# Stim_EMG_breakout.net
KiCad netlist of a schematic drawn in EAGLE
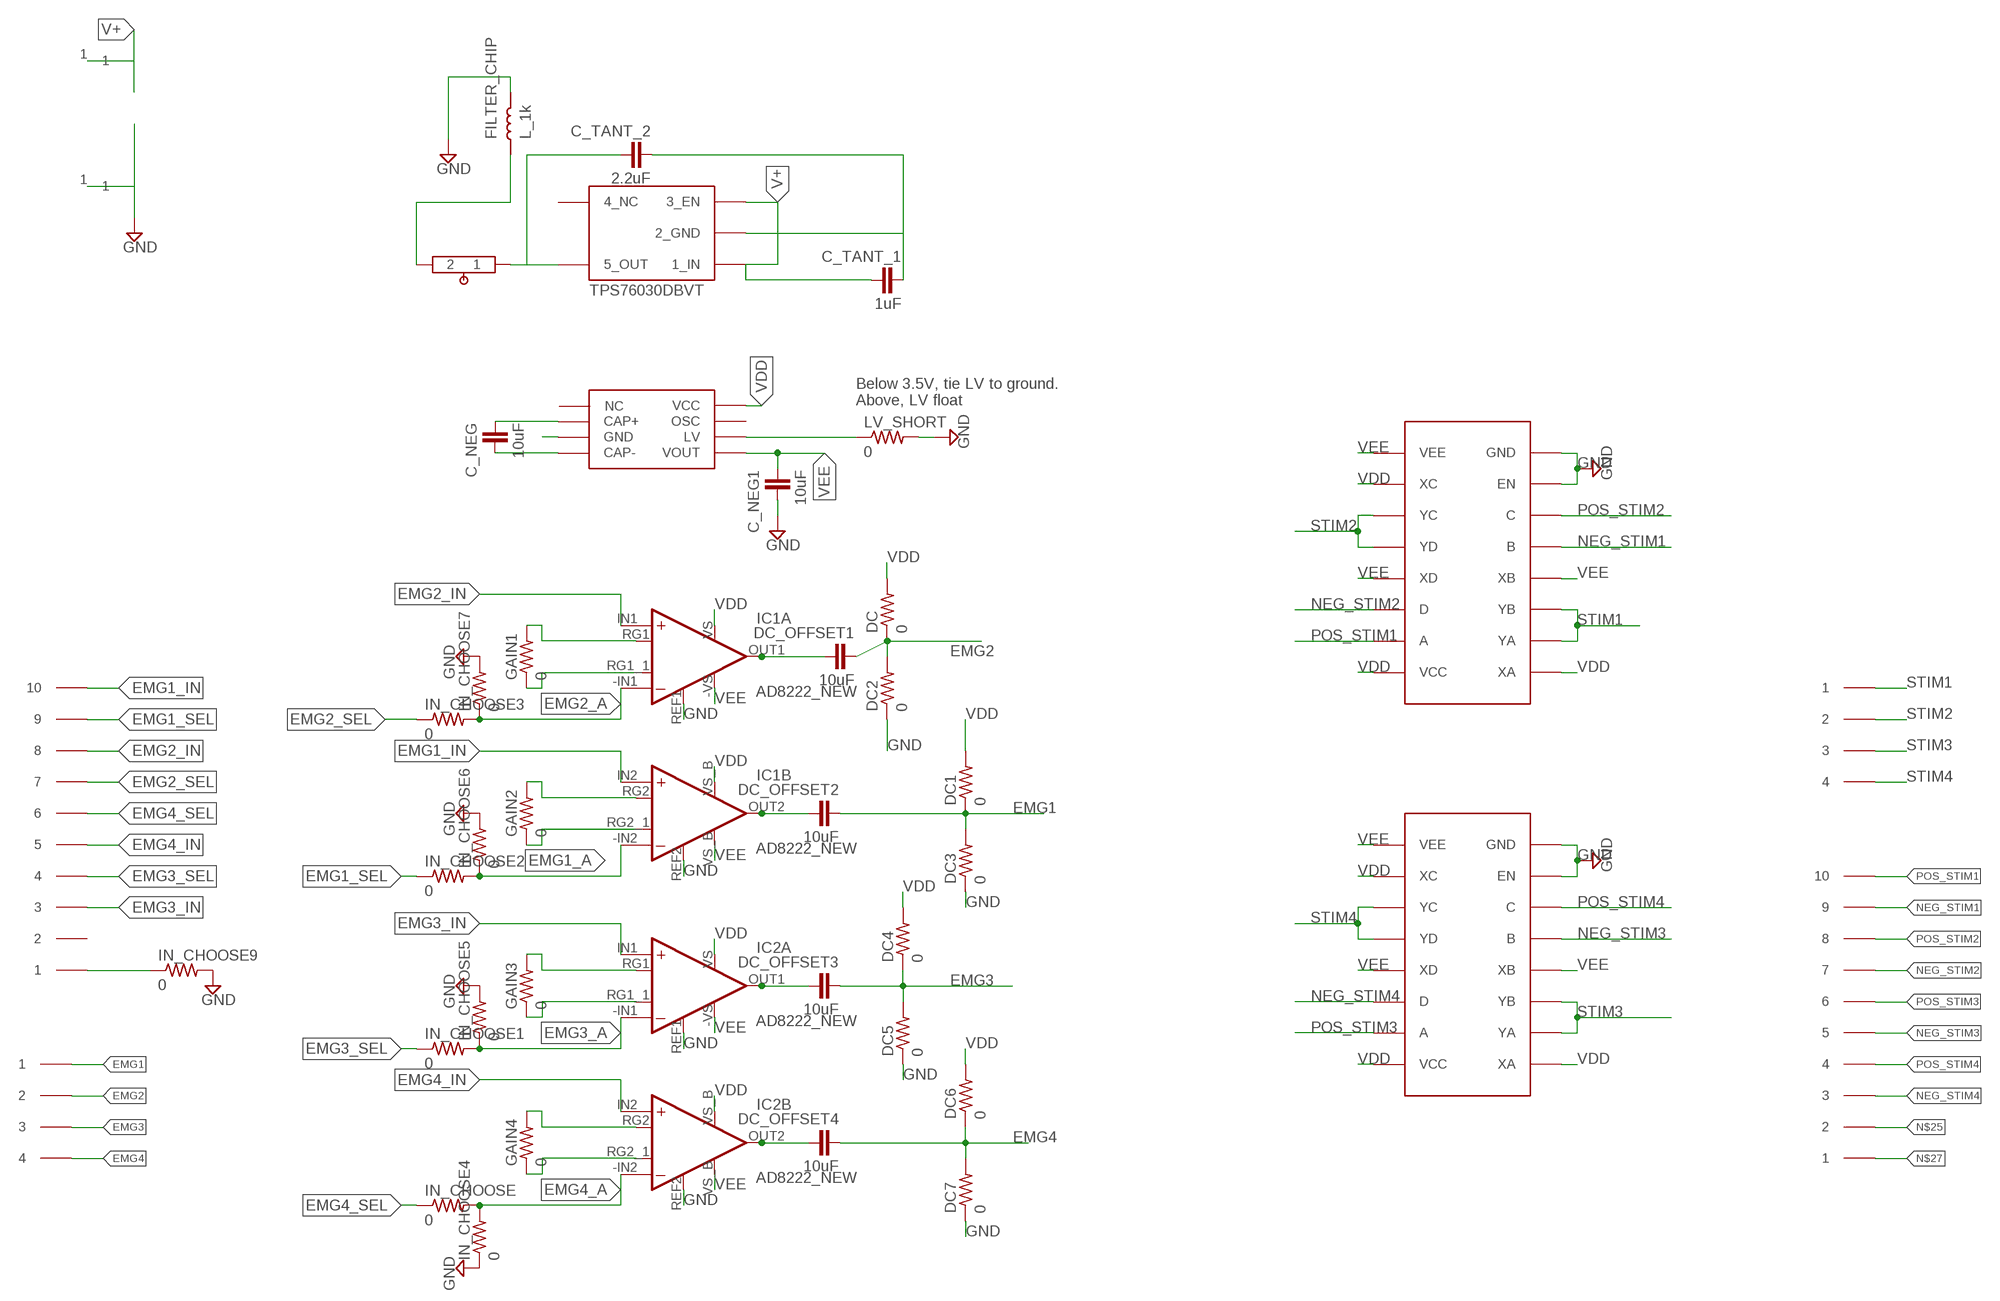
[diagram p0: schematic, sheet 1]

(export (version "E")
  (design (tool "Eeschema 10.0.6"))
  (components
    (comp (ref "C_NEG")
      (value "10uF")
      (footprint "eagle-import:0402_R_L_C")
      (libsource (lib "eagle-import") (part "0Y0X_C0402"))
    )
    (comp (ref "C_NEG1")
      (value "10uF")
      (footprint "eagle-import:0402_R_L_C")
      (libsource (lib "eagle-import") (part "0Y0X_C0402"))
    )
    (comp (ref "C_TANT_1")
      (value "1uF")
      (footprint "eagle-import:0603_R_L_C")
      (libsource (lib "eagle-import") (part "0Y0X_C0603"))
    )
    (comp (ref "C_TANT_2")
      (value "2.2uF")
      (footprint "eagle-import:0603_R_L_C")
      (libsource (lib "eagle-import") (part "0Y0X_C0603"))
    )
    (comp (ref "DC")
      (value "0")
      (footprint "eagle-import:0402_R_L_C")
      (libsource (lib "eagle-import") (part "0Y0X_R0402"))
    )
    (comp (ref "DC1")
      (value "0")
      (footprint "eagle-import:0402_R_L_C")
      (libsource (lib "eagle-import") (part "0Y0X_R0402"))
    )
    (comp (ref "DC2")
      (value "0")
      (footprint "eagle-import:0402_R_L_C")
      (libsource (lib "eagle-import") (part "0Y0X_R0402"))
    )
    (comp (ref "DC3")
      (value "0")
      (footprint "eagle-import:0402_R_L_C")
      (libsource (lib "eagle-import") (part "0Y0X_R0402"))
    )
    (comp (ref "DC4")
      (value "0")
      (footprint "eagle-import:0402_R_L_C")
      (libsource (lib "eagle-import") (part "0Y0X_R0402"))
    )
    (comp (ref "DC5")
      (value "0")
      (footprint "eagle-import:0402_R_L_C")
      (libsource (lib "eagle-import") (part "0Y0X_R0402"))
    )
    (comp (ref "DC6")
      (value "0")
      (footprint "eagle-import:0402_R_L_C")
      (libsource (lib "eagle-import") (part "0Y0X_R0402"))
    )
    (comp (ref "DC7")
      (value "0")
      (footprint "eagle-import:0402_R_L_C")
      (libsource (lib "eagle-import") (part "0Y0X_R0402"))
    )
    (comp (ref "DC_OFFSET1")
      (value "10uF")
      (footprint "eagle-import:0402_R_L_C")
      (libsource (lib "eagle-import") (part "0Y0X_C0402"))
    )
    (comp (ref "DC_OFFSET2")
      (value "10uF")
      (footprint "eagle-import:0402_R_L_C")
      (libsource (lib "eagle-import") (part "0Y0X_C0402"))
    )
    (comp (ref "DC_OFFSET3")
      (value "10uF")
      (footprint "eagle-import:0402_R_L_C")
      (libsource (lib "eagle-import") (part "0Y0X_C0402"))
    )
    (comp (ref "DC_OFFSET4")
      (value "10uF")
      (footprint "eagle-import:0402_R_L_C")
      (libsource (lib "eagle-import") (part "0Y0X_C0402"))
    )
    (comp (ref "FILTER_CHIP")
      (value "L_1k")
      (footprint "eagle-import:0402_R_L_C")
      (libsource (lib "eagle-import") (part "0Y0X_L0402"))
    )
    (comp (ref "GAIN1")
      (value "0")
      (footprint "eagle-import:0402_R_L_C")
      (libsource (lib "eagle-import") (part "0Y0X_R0402"))
    )
    (comp (ref "GAIN2")
      (value "0")
      (footprint "eagle-import:0402_R_L_C")
      (libsource (lib "eagle-import") (part "0Y0X_R0402"))
    )
    (comp (ref "GAIN3")
      (value "0")
      (footprint "eagle-import:0402_R_L_C")
      (libsource (lib "eagle-import") (part "0Y0X_R0402"))
    )
    (comp (ref "GAIN4")
      (value "0")
      (footprint "eagle-import:0402_R_L_C")
      (libsource (lib "eagle-import") (part "0Y0X_R0402"))
    )
    (comp (ref "IC1")
      (value "AD8222_NEW")
      (footprint "eagle-import:QFN-16")
      (libsource (lib "eagle-import") (part "AD8222_NEW"))
    )
    (comp (ref "IC2")
      (value "AD8222_NEW")
      (footprint "eagle-import:QFN-16")
      (libsource (lib "eagle-import") (part "AD8222_NEW"))
    )
    (comp (ref "IN_CHOOSE")
      (value "0")
      (footprint "eagle-import:0201_R_L_C")
      (libsource (lib "eagle-import") (part "0Y0X_R0201"))
    )
    (comp (ref "IN_CHOOSE1")
      (value "0")
      (footprint "eagle-import:0201_R_L_C")
      (libsource (lib "eagle-import") (part "0Y0X_R0201"))
    )
    (comp (ref "IN_CHOOSE2")
      (value "0")
      (footprint "eagle-import:0201_R_L_C")
      (libsource (lib "eagle-import") (part "0Y0X_R0201"))
    )
    (comp (ref "IN_CHOOSE3")
      (value "0")
      (footprint "eagle-import:0201_R_L_C")
      (libsource (lib "eagle-import") (part "0Y0X_R0201"))
    )
    (comp (ref "IN_CHOOSE4")
      (value "0")
      (footprint "eagle-import:0201_R_L_C")
      (libsource (lib "eagle-import") (part "0Y0X_R0201"))
    )
    (comp (ref "IN_CHOOSE5")
      (value "0")
      (footprint "eagle-import:0201_R_L_C")
      (libsource (lib "eagle-import") (part "0Y0X_R0201"))
    )
    (comp (ref "IN_CHOOSE6")
      (value "0")
      (footprint "eagle-import:0201_R_L_C")
      (libsource (lib "eagle-import") (part "0Y0X_R0201"))
    )
    (comp (ref "IN_CHOOSE7")
      (value "0")
      (footprint "eagle-import:0201_R_L_C")
      (libsource (lib "eagle-import") (part "0Y0X_R0201"))
    )
    (comp (ref "IN_CHOOSE9")
      (value "0")
      (footprint "eagle-import:0201_R_L_C")
      (libsource (lib "eagle-import") (part "0Y0X_R0201"))
    )
    (comp (ref "LV_SHORT")
      (value "0")
      (footprint "eagle-import:0402_R_L_C")
      (libsource (lib "eagle-import") (part "0Y0X_R0402"))
    )
    (comp (ref "U$1")
      (value "FFC10POS")
      (footprint "eagle-import:FFC10POS")
      (libsource (lib "eagle-import") (part "FFC10POS"))
    )
    (comp (ref "U$2")
      (value "FFC4POS")
      (footprint "eagle-import:FFC4POS")
      (libsource (lib "eagle-import") (part "FFC4POS"))
    )
    (comp (ref "U$4")
      (value "TL7660")
      (footprint "eagle-import:S-PDSO-G8")
      (libsource (lib "eagle-import") (part "TL7660"))
    )
    (comp (ref "U$5")
      (value "MC74HC4316A")
      (footprint "eagle-import:SOIC-16-ON-SEMI")
      (libsource (lib "eagle-import") (part "MC74HC4316A"))
    )
    (comp (ref "U$6")
      (value "MC74HC4316A")
      (footprint "eagle-import:SOIC-16-ON-SEMI")
      (libsource (lib "eagle-import") (part "MC74HC4316A"))
    )
    (comp (ref "U$7")
      (value "FFC10POS")
      (footprint "eagle-import:FFC10POS")
      (libsource (lib "eagle-import") (part "FFC10POS"))
    )
    (comp (ref "U$10")
      (value "REGULATOR")
      (footprint "eagle-import:REGULATOR")
      (libsource (lib "eagle-import") (part "REGULATOR"))
    )
    (comp (ref "U$18")
      (value "SWITCH_MANUAL")
      (footprint "eagle-import:SWITCH_MANUAL")
      (libsource (lib "eagle-import") (part "SWITCH_MANUAL"))
    )
    (comp (ref "U$28")
      (value "FFC4POS")
      (footprint "eagle-import:FFC4POS")
      (libsource (lib "eagle-import") (part "FFC4POS"))
    )
    (comp (ref "WIRE+")
      (value "DRILL_CONNECT")
      (footprint "eagle-import:DRILL_CONNECT")
      (libsource (lib "eagle-import") (part "DRILL_CONNECT"))
    )
    (comp (ref "WIRE-")
      (value "DRILL_CONNECT")
      (footprint "eagle-import:DRILL_CONNECT")
      (libsource (lib "eagle-import") (part "DRILL_CONNECT"))
    )
  )
  (nets
    (net (code "1") (name "/NC") (class "Default")
      (node (ref "U$4") (pin "1") (pinfunction "NC_1") (pintype "power_in"))
    )
    (net (code "2") (name "/OSC") (class "Default")
      (node (ref "U$4") (pin "7") (pinfunction "OSC_7") (pintype "power_in"))
    )
    (net (code "3") (name "/STIM1") (class "Default")
      (node (ref "U$28") (pin "1") (pinfunction "1_1") (pintype "bidirectional"))
      (node (ref "U$5") (pin "2") (pinfunction "YA_2") (pintype "output"))
      (node (ref "U$5") (pin "3") (pinfunction "YB_3") (pintype "output"))
    )
    (net (code "4") (name "/STIM2") (class "Default")
      (node (ref "U$28") (pin "2") (pinfunction "2_2") (pintype "bidirectional"))
      (node (ref "U$5") (pin "11") (pinfunction "YC_11") (pintype "output"))
      (node (ref "U$5") (pin "12") (pinfunction "YD_12") (pintype "output"))
    )
    (net (code "5") (name "/STIM3") (class "Default")
      (node (ref "U$28") (pin "3") (pinfunction "3_3") (pintype "bidirectional"))
      (node (ref "U$6") (pin "2") (pinfunction "YA_2") (pintype "output"))
      (node (ref "U$6") (pin "3") (pinfunction "YB_3") (pintype "output"))
    )
    (net (code "6") (name "/STIM4") (class "Default")
      (node (ref "U$28") (pin "4") (pinfunction "4_4") (pintype "bidirectional"))
      (node (ref "U$6") (pin "11") (pinfunction "YC_11") (pintype "output"))
      (node (ref "U$6") (pin "12") (pinfunction "YD_12") (pintype "output"))
    )
    (net (code "7") (name "EMG1") (class "Default")
      (node (ref "DC1") (pin "1") (pinfunction "1_1") (pintype "passive"))
      (node (ref "DC3") (pin "2") (pinfunction "2_2") (pintype "passive"))
      (node (ref "DC_OFFSET2") (pin "2") (pinfunction "2_2") (pintype "passive"))
      (node (ref "U$2") (pin "1") (pinfunction "1_1") (pintype "bidirectional"))
    )
    (net (code "8") (name "EMG1_A") (class "Default")
      (node (ref "IC1") (pin "-IN2") (pinfunction "-IN_-IN2") (pintype "input"))
      (node (ref "IN_CHOOSE2") (pin "2") (pinfunction "2_2") (pintype "passive"))
      (node (ref "IN_CHOOSE6") (pin "1") (pinfunction "1_1") (pintype "passive"))
    )
    (net (code "9") (name "EMG1_IN") (class "Default")
      (node (ref "IC1") (pin "IN2") (pinfunction "+IN_IN2") (pintype "input"))
      (node (ref "U$7") (pin "10") (pinfunction "10_10") (pintype "bidirectional"))
    )
    (net (code "10") (name "EMG1_SEL") (class "Default")
      (node (ref "IN_CHOOSE2") (pin "1") (pinfunction "1_1") (pintype "passive"))
      (node (ref "U$7") (pin "9") (pinfunction "9_9") (pintype "bidirectional"))
    )
    (net (code "11") (name "EMG2") (class "Default")
      (node (ref "DC") (pin "1") (pinfunction "1_1") (pintype "passive"))
      (node (ref "DC2") (pin "2") (pinfunction "2_2") (pintype "passive"))
      (node (ref "DC_OFFSET1") (pin "2") (pinfunction "2_2") (pintype "passive"))
      (node (ref "U$2") (pin "2") (pinfunction "2_2") (pintype "bidirectional"))
    )
    (net (code "12") (name "EMG2_A") (class "Default")
      (node (ref "IC1") (pin "-IN1") (pinfunction "-IN_-IN1") (pintype "input"))
      (node (ref "IN_CHOOSE3") (pin "2") (pinfunction "2_2") (pintype "passive"))
      (node (ref "IN_CHOOSE7") (pin "1") (pinfunction "1_1") (pintype "passive"))
    )
    (net (code "13") (name "EMG2_IN") (class "Default")
      (node (ref "IC1") (pin "IN1") (pinfunction "+IN_IN1") (pintype "input"))
      (node (ref "U$7") (pin "8") (pinfunction "8_8") (pintype "bidirectional"))
    )
    (net (code "14") (name "EMG2_SEL") (class "Default")
      (node (ref "IN_CHOOSE3") (pin "1") (pinfunction "1_1") (pintype "passive"))
      (node (ref "U$7") (pin "7") (pinfunction "7_7") (pintype "bidirectional"))
    )
    (net (code "15") (name "EMG3") (class "Default")
      (node (ref "DC4") (pin "1") (pinfunction "1_1") (pintype "passive"))
      (node (ref "DC5") (pin "2") (pinfunction "2_2") (pintype "passive"))
      (node (ref "DC_OFFSET3") (pin "2") (pinfunction "2_2") (pintype "passive"))
      (node (ref "U$2") (pin "3") (pinfunction "3_3") (pintype "bidirectional"))
    )
    (net (code "16") (name "EMG3_A") (class "Default")
      (node (ref "IC2") (pin "-IN1") (pinfunction "-IN_-IN1") (pintype "input"))
      (node (ref "IN_CHOOSE1") (pin "2") (pinfunction "2_2") (pintype "passive"))
      (node (ref "IN_CHOOSE5") (pin "1") (pinfunction "1_1") (pintype "passive"))
    )
    (net (code "17") (name "EMG3_IN") (class "Default")
      (node (ref "IC2") (pin "IN1") (pinfunction "+IN_IN1") (pintype "input"))
      (node (ref "U$7") (pin "3") (pinfunction "3_3") (pintype "bidirectional"))
    )
    (net (code "18") (name "EMG3_SEL") (class "Default")
      (node (ref "IN_CHOOSE1") (pin "1") (pinfunction "1_1") (pintype "passive"))
      (node (ref "U$7") (pin "4") (pinfunction "4_4") (pintype "bidirectional"))
    )
    (net (code "19") (name "EMG4") (class "Default")
      (node (ref "DC6") (pin "1") (pinfunction "1_1") (pintype "passive"))
      (node (ref "DC7") (pin "2") (pinfunction "2_2") (pintype "passive"))
      (node (ref "DC_OFFSET4") (pin "2") (pinfunction "2_2") (pintype "passive"))
      (node (ref "U$2") (pin "4") (pinfunction "4_4") (pintype "bidirectional"))
    )
    (net (code "20") (name "EMG4_A") (class "Default")
      (node (ref "IC2") (pin "-IN2") (pinfunction "-IN_-IN2") (pintype "input"))
      (node (ref "IN_CHOOSE") (pin "2") (pinfunction "2_2") (pintype "passive"))
      (node (ref "IN_CHOOSE4") (pin "2") (pinfunction "2_2") (pintype "passive"))
    )
    (net (code "21") (name "EMG4_IN") (class "Default")
      (node (ref "IC2") (pin "IN2") (pinfunction "+IN_IN2") (pintype "input"))
      (node (ref "U$7") (pin "5") (pinfunction "5_5") (pintype "bidirectional"))
    )
    (net (code "22") (name "EMG4_SEL") (class "Default")
      (node (ref "IN_CHOOSE") (pin "1") (pinfunction "1_1") (pintype "passive"))
      (node (ref "U$7") (pin "6") (pinfunction "6_6") (pintype "bidirectional"))
    )
    (net (code "23") (name "GND") (class "Default")
      (node (ref "C_NEG1") (pin "1") (pinfunction "1_1") (pintype "passive"))
      (node (ref "DC2") (pin "1") (pinfunction "1_1") (pintype "passive"))
      (node (ref "DC3") (pin "1") (pinfunction "1_1") (pintype "passive"))
      (node (ref "DC5") (pin "1") (pinfunction "1_1") (pintype "passive"))
      (node (ref "DC7") (pin "1") (pinfunction "1_1") (pintype "passive"))
      (node (ref "FILTER_CHIP") (pin "2") (pinfunction "2_2") (pintype "bidirectional"))
      (node (ref "IC1") (pin "REF1") (pinfunction "REF_REF1") (pintype "input"))
      (node (ref "IC1") (pin "REF2") (pinfunction "REF_REF2") (pintype "input"))
      (node (ref "IC2") (pin "REF1") (pinfunction "REF_REF1") (pintype "input"))
      (node (ref "IC2") (pin "REF2") (pinfunction "REF_REF2") (pintype "input"))
      (node (ref "IN_CHOOSE4") (pin "1") (pinfunction "1_1") (pintype "passive"))
      (node (ref "IN_CHOOSE5") (pin "2") (pinfunction "2_2") (pintype "passive"))
      (node (ref "IN_CHOOSE6") (pin "2") (pinfunction "2_2") (pintype "passive"))
      (node (ref "IN_CHOOSE7") (pin "2") (pinfunction "2_2") (pintype "passive"))
      (node (ref "IN_CHOOSE9") (pin "2") (pinfunction "2_2") (pintype "passive"))
      (node (ref "LV_SHORT") (pin "2") (pinfunction "2_2") (pintype "passive"))
      (node (ref "U$4") (pin "3") (pinfunction "GND_3") (pintype "power_in"))
      (node (ref "U$5") (pin "7") (pinfunction "EN_7") (pintype "input"))
      (node (ref "U$5") (pin "8") (pinfunction "GND_8") (pintype "power_in"))
      (node (ref "U$6") (pin "7") (pinfunction "EN_7") (pintype "input"))
      (node (ref "U$6") (pin "8") (pinfunction "GND_8") (pintype "power_in"))
      (node (ref "WIRE-") (pin "1") (pinfunction "1_1") (pintype "bidirectional"))
    )
    (net (code "24") (name "N$25") (class "Default")
      (node (ref "U$1") (pin "2") (pinfunction "2_2") (pintype "bidirectional"))
    )
    (net (code "25") (name "N$27") (class "Default")
      (node (ref "U$1") (pin "1") (pinfunction "1_1") (pintype "bidirectional"))
    )
    (net (code "26") (name "NEG_STIM1") (class "Default")
      (node (ref "U$1") (pin "9") (pinfunction "9_9") (pintype "bidirectional"))
      (node (ref "U$5") (pin "5") (pinfunction "B_5") (pintype "input"))
    )
    (net (code "27") (name "NEG_STIM2") (class "Default")
      (node (ref "U$1") (pin "7") (pinfunction "7_7") (pintype "bidirectional"))
      (node (ref "U$5") (pin "14") (pinfunction "D_14") (pintype "input"))
    )
    (net (code "28") (name "NEG_STIM3") (class "Default")
      (node (ref "U$1") (pin "5") (pinfunction "5_5") (pintype "bidirectional"))
      (node (ref "U$6") (pin "5") (pinfunction "B_5") (pintype "input"))
    )
    (net (code "29") (name "NEG_STIM4") (class "Default")
      (node (ref "U$1") (pin "3") (pinfunction "3_3") (pintype "bidirectional"))
      (node (ref "U$6") (pin "14") (pinfunction "D_14") (pintype "input"))
    )
    (net (code "30") (name "Net-(GAIN1-Pad1)") (class "Default")
      (node (ref "GAIN1") (pin "1") (pinfunction "1_1") (pintype "passive"))
      (node (ref "IC1") (pin "RG1_1") (pinfunction "RG1_1_RG1_1") (pintype "input"))
    )
    (net (code "31") (name "Net-(GAIN1-Pad2)") (class "Default")
      (node (ref "GAIN1") (pin "2") (pinfunction "2_2") (pintype "passive"))
      (node (ref "IC1") (pin "RG1") (pinfunction "RG1_RG1") (pintype "input"))
    )
    (net (code "32") (name "Net-(GAIN3-Pad1)") (class "Default")
      (node (ref "GAIN3") (pin "1") (pinfunction "1_1") (pintype "passive"))
      (node (ref "IC2") (pin "RG1_1") (pinfunction "RG1_1_RG1_1") (pintype "input"))
    )
    (net (code "33") (name "Net-(GAIN3-Pad2)") (class "Default")
      (node (ref "GAIN3") (pin "2") (pinfunction "2_2") (pintype "passive"))
      (node (ref "IC2") (pin "RG1") (pinfunction "RG1_RG1") (pintype "input"))
    )
    (net (code "34") (name "Net-(IC1A-OUT)") (class "Default")
      (node (ref "DC_OFFSET1") (pin "1") (pinfunction "1_1") (pintype "passive"))
      (node (ref "IC1") (pin "OUT1") (pinfunction "OUT_OUT1") (pintype "input"))
    )
    (net (code "35") (name "Net-(IC1B-OUT)") (class "Default")
      (node (ref "DC_OFFSET2") (pin "1") (pinfunction "1_1") (pintype "passive"))
      (node (ref "IC1") (pin "OUT2") (pinfunction "OUT_OUT2") (pintype "input"))
    )
    (net (code "36") (name "Net-(IC1B-RG1)") (class "Default")
      (node (ref "GAIN2") (pin "2") (pinfunction "2_2") (pintype "passive"))
      (node (ref "IC1") (pin "RG2") (pinfunction "RG1_RG2") (pintype "input"))
    )
    (net (code "37") (name "Net-(IC1B-RG1_1)") (class "Default")
      (node (ref "GAIN2") (pin "1") (pinfunction "1_1") (pintype "passive"))
      (node (ref "IC1") (pin "RG2_1") (pinfunction "RG1_1_RG2_1") (pintype "input"))
    )
    (net (code "38") (name "Net-(IC2A-OUT)") (class "Default")
      (node (ref "DC_OFFSET3") (pin "1") (pinfunction "1_1") (pintype "passive"))
      (node (ref "IC2") (pin "OUT1") (pinfunction "OUT_OUT1") (pintype "input"))
    )
    (net (code "39") (name "Net-(IC2B-OUT)") (class "Default")
      (node (ref "DC_OFFSET4") (pin "1") (pinfunction "1_1") (pintype "passive"))
      (node (ref "IC2") (pin "OUT2") (pinfunction "OUT_OUT2") (pintype "input"))
    )
    (net (code "40") (name "Net-(IC2B-RG1)") (class "Default")
      (node (ref "GAIN4") (pin "2") (pinfunction "2_2") (pintype "passive"))
      (node (ref "IC2") (pin "RG2") (pinfunction "RG1_RG2") (pintype "input"))
    )
    (net (code "41") (name "Net-(IC2B-RG1_1)") (class "Default")
      (node (ref "GAIN4") (pin "1") (pinfunction "1_1") (pintype "passive"))
      (node (ref "IC2") (pin "RG2_1") (pinfunction "RG1_1_RG2_1") (pintype "input"))
    )
    (net (code "42") (name "Net-(IN_CHOOSE9-Pad1)") (class "Default")
      (node (ref "IN_CHOOSE9") (pin "1") (pinfunction "1_1") (pintype "passive"))
      (node (ref "U$7") (pin "1") (pinfunction "1_1") (pintype "bidirectional"))
    )
    (net (code "43") (name "Net-(U$4-CAP+)") (class "Default")
      (node (ref "C_NEG") (pin "2") (pinfunction "2_2") (pintype "passive"))
      (node (ref "U$4") (pin "2") (pinfunction "CAP+_2") (pintype "power_in"))
    )
    (net (code "44") (name "Net-(U$4-CAP-)") (class "Default")
      (node (ref "C_NEG") (pin "1") (pinfunction "1_1") (pintype "passive"))
      (node (ref "U$4") (pin "4") (pinfunction "CAP-_4") (pintype "power_in"))
    )
    (net (code "45") (name "Net-(U$4-LV)") (class "Default")
      (node (ref "LV_SHORT") (pin "1") (pinfunction "1_1") (pintype "passive"))
      (node (ref "U$4") (pin "6") (pinfunction "LV_6") (pintype "power_in"))
    )
    (net (code "46") (name "Net-(U$10-2_GND)") (class "Default")
      (node (ref "C_TANT_1") (pin "2") (pinfunction "2_2") (pintype "passive"))
      (node (ref "C_TANT_2") (pin "2") (pinfunction "2_2") (pintype "passive"))
      (node (ref "U$10") (pin "2") (pinfunction "2_GND_2") (pintype "power_in"))
    )
    (net (code "47") (name "Net-(U$10-5_OUT)") (class "Default")
      (node (ref "C_TANT_2") (pin "1") (pinfunction "1_1") (pintype "passive"))
      (node (ref "U$10") (pin "5") (pinfunction "5_OUT_5") (pintype "bidirectional"))
      (node (ref "U$18") (pin "1") (pinfunction "1_1") (pintype "bidirectional"))
    )
    (net (code "48") (name "POS_STIM1") (class "Default")
      (node (ref "U$1") (pin "10") (pinfunction "10_10") (pintype "bidirectional"))
      (node (ref "U$5") (pin "15") (pinfunction "A_15") (pintype "input"))
    )
    (net (code "49") (name "POS_STIM2") (class "Default")
      (node (ref "U$1") (pin "8") (pinfunction "8_8") (pintype "bidirectional"))
      (node (ref "U$5") (pin "6") (pinfunction "C_6") (pintype "input"))
    )
    (net (code "50") (name "POS_STIM3") (class "Default")
      (node (ref "U$1") (pin "6") (pinfunction "6_6") (pintype "bidirectional"))
      (node (ref "U$6") (pin "15") (pinfunction "A_15") (pintype "input"))
    )
    (net (code "51") (name "POS_STIM4") (class "Default")
      (node (ref "U$1") (pin "4") (pinfunction "4_4") (pintype "bidirectional"))
      (node (ref "U$6") (pin "6") (pinfunction "C_6") (pintype "input"))
    )
    (net (code "52") (name "V+") (class "Default")
      (node (ref "C_TANT_1") (pin "1") (pinfunction "1_1") (pintype "passive"))
      (node (ref "U$10") (pin "1") (pinfunction "1_IN_1") (pintype "bidirectional"))
      (node (ref "U$10") (pin "3") (pinfunction "3_EN_3") (pintype "bidirectional"))
      (node (ref "WIRE+") (pin "1") (pinfunction "1_1") (pintype "bidirectional"))
    )
    (net (code "53") (name "VDD") (class "Default")
      (node (ref "DC") (pin "2") (pinfunction "2_2") (pintype "passive"))
      (node (ref "DC1") (pin "2") (pinfunction "2_2") (pintype "passive"))
      (node (ref "DC4") (pin "2") (pinfunction "2_2") (pintype "passive"))
      (node (ref "DC6") (pin "2") (pinfunction "2_2") (pintype "passive"))
      (node (ref "FILTER_CHIP") (pin "1") (pinfunction "1_1") (pintype "bidirectional"))
      (node (ref "IC1") (pin "VS") (pinfunction "V+_VS") (pintype "power_in"))
      (node (ref "IC1") (pin "VS_B") (pinfunction "V+_VS_B") (pintype "power_in"))
      (node (ref "IC2") (pin "VS") (pinfunction "V+_VS") (pintype "power_in"))
      (node (ref "IC2") (pin "VS_B") (pinfunction "V+_VS_B") (pintype "power_in"))
      (node (ref "U$18") (pin "2") (pinfunction "2_2") (pintype "bidirectional"))
      (node (ref "U$4") (pin "8") (pinfunction "VCC_8") (pintype "power_in"))
      (node (ref "U$5") (pin "1") (pinfunction "XA_1") (pintype "input"))
      (node (ref "U$5") (pin "10") (pinfunction "XC_10") (pintype "input"))
      (node (ref "U$5") (pin "16") (pinfunction "VCC_16") (pintype "power_in"))
      (node (ref "U$6") (pin "1") (pinfunction "XA_1") (pintype "input"))
      (node (ref "U$6") (pin "10") (pinfunction "XC_10") (pintype "input"))
      (node (ref "U$6") (pin "16") (pinfunction "VCC_16") (pintype "power_in"))
    )
    (net (code "54") (name "VEE") (class "Default")
      (node (ref "C_NEG1") (pin "2") (pinfunction "2_2") (pintype "passive"))
      (node (ref "IC1") (pin "-VS") (pinfunction "V-_-VS") (pintype "power_in"))
      (node (ref "IC1") (pin "-VS_B") (pinfunction "V-_-VS_B") (pintype "power_in"))
      (node (ref "IC2") (pin "-VS") (pinfunction "V-_-VS") (pintype "power_in"))
      (node (ref "IC2") (pin "-VS_B") (pinfunction "V-_-VS_B") (pintype "power_in"))
      (node (ref "U$4") (pin "5") (pinfunction "VOUT_5") (pintype "power_in"))
      (node (ref "U$5") (pin "13") (pinfunction "XD_13") (pintype "input"))
      (node (ref "U$5") (pin "4") (pinfunction "XB_4") (pintype "input"))
      (node (ref "U$5") (pin "9") (pinfunction "VEE_9") (pintype "power_in"))
      (node (ref "U$6") (pin "13") (pinfunction "XD_13") (pintype "input"))
      (node (ref "U$6") (pin "4") (pinfunction "XB_4") (pintype "input"))
      (node (ref "U$6") (pin "9") (pinfunction "VEE_9") (pintype "power_in"))
    )
    (net (code "55") (name "unconnected-(U$7-Pad2)") (class "Default")
      (node (ref "U$7") (pin "2") (pinfunction "2_2") (pintype "bidirectional"))
    )
    (net (code "56") (name "unconnected-(U$10-4_NC-Pad4)") (class "Default")
      (node (ref "U$10") (pin "4") (pinfunction "4_NC_4") (pintype "no_connect"))
    )
  )
)
